# Arm_Schematic.net
KiCad netlist of a schematic drawn in Altium Designer
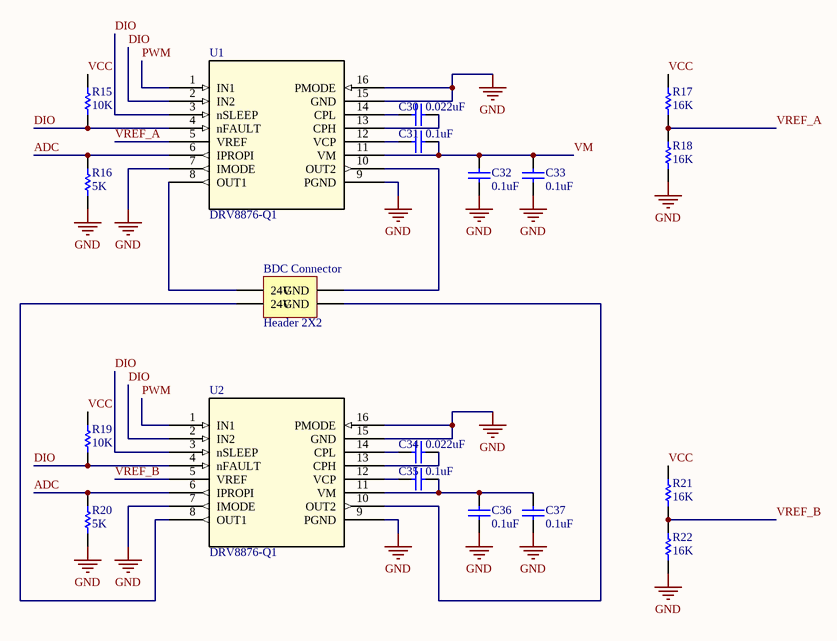
[diagram p0: Arm Schematic.SchDoc]

(export (version "E")
  (design (tool "Eeschema 10.0.6"))
  (components
    (comp (ref "BDC Connector")
      (value "Header 2X2")
      (footprint "MHDR2X2")
      (description "Header, 2-Pin, Dual row")
      (fields (field (name "PUBLISHER") "Altium Limited"))
      (libsource (lib "Miscellaneous Connectors") (part "MHDR2X2"))
    )
    (comp (ref "C30")
      (value "0.022uF")
      (footprint "CAP_1206")
      (description "Capacitor 1208 22uF")
      (fields
        (field (name "MANUFACTURER") "Samsung Electro-Mechanics America, Inc")
        (field (name "MANUFACTURER PART NUMBER") "CL31A226MOCLNNC")
      )
      (libsource (lib "Capacitors") (part "22uF_16V_1208"))
    )
    (comp (ref "C31")
      (value "0.1uF")
      (footprint "CAP_1206")
      (description "Capacitor 1208 22uF")
      (fields
        (field (name "MANUFACTURER") "Samsung Electro-Mechanics America, Inc")
        (field (name "MANUFACTURER PART NUMBER") "CL31A226MOCLNNC")
      )
      (libsource (lib "Capacitors") (part "22uF_16V_1208"))
    )
    (comp (ref "C32")
      (value "0.1uF")
      (footprint "CAP_1206")
      (description "Capacitor 1208 22uF")
      (fields
        (field (name "MANUFACTURER") "Samsung Electro-Mechanics America, Inc")
        (field (name "MANUFACTURER PART NUMBER") "CL31A226MOCLNNC")
      )
      (libsource (lib "Capacitors") (part "22uF_16V_1208"))
    )
    (comp (ref "C33")
      (value "0.1uF")
      (footprint "CAP_1206")
      (description "Capacitor 1208 22uF")
      (fields
        (field (name "MANUFACTURER") "Samsung Electro-Mechanics America, Inc")
        (field (name "MANUFACTURER PART NUMBER") "CL31A226MOCLNNC")
      )
      (libsource (lib "Capacitors") (part "22uF_16V_1208"))
    )
    (comp (ref "C34")
      (value "0.022uF")
      (footprint "CAP_1206")
      (description "Capacitor 1208 22uF")
      (fields
        (field (name "MANUFACTURER") "Samsung Electro-Mechanics America, Inc")
        (field (name "MANUFACTURER PART NUMBER") "CL31A226MOCLNNC")
      )
      (libsource (lib "Capacitors") (part "22uF_16V_1208"))
    )
    (comp (ref "C35")
      (value "0.1uF")
      (footprint "CAP_1206")
      (description "Capacitor 1208 22uF")
      (fields
        (field (name "MANUFACTURER") "Samsung Electro-Mechanics America, Inc")
        (field (name "MANUFACTURER PART NUMBER") "CL31A226MOCLNNC")
      )
      (libsource (lib "Capacitors") (part "22uF_16V_1208"))
    )
    (comp (ref "C36")
      (value "0.1uF")
      (footprint "CAP_1206")
      (description "Capacitor 1208 22uF")
      (fields
        (field (name "MANUFACTURER") "Samsung Electro-Mechanics America, Inc")
        (field (name "MANUFACTURER PART NUMBER") "CL31A226MOCLNNC")
      )
      (libsource (lib "Capacitors") (part "22uF_16V_1208"))
    )
    (comp (ref "C37")
      (value "0.1uF")
      (footprint "CAP_1206")
      (description "Capacitor 1208 22uF")
      (fields
        (field (name "MANUFACTURER") "Samsung Electro-Mechanics America, Inc")
        (field (name "MANUFACTURER PART NUMBER") "CL31A226MOCLNNC")
      )
      (libsource (lib "Capacitors") (part "22uF_16V_1208"))
    )
    (comp (ref "R15")
      (value "10K")
      (footprint "AXIAL-0.3")
      (description "Resistor")
      (fields (field (name "PUBLISHER") "Altium Limited"))
      (libsource (lib "Miscellaneous Devices") (part "Res1"))
    )
    (comp (ref "R16")
      (value "5K")
      (footprint "AXIAL-0.3")
      (description "Resistor")
      (fields (field (name "PUBLISHER") "Altium Limited"))
      (libsource (lib "Miscellaneous Devices") (part "Res1"))
    )
    (comp (ref "R17")
      (value "16K")
      (footprint "AXIAL-0.3")
      (description "Resistor")
      (fields (field (name "PUBLISHER") "Altium Limited"))
      (libsource (lib "Miscellaneous Devices") (part "Res1"))
    )
    (comp (ref "R18")
      (value "16K")
      (footprint "AXIAL-0.3")
      (description "Resistor")
      (fields (field (name "PUBLISHER") "Altium Limited"))
      (libsource (lib "Miscellaneous Devices") (part "Res1"))
    )
    (comp (ref "R19")
      (value "10K")
      (footprint "AXIAL-0.3")
      (description "Resistor")
      (fields (field (name "PUBLISHER") "Altium Limited"))
      (libsource (lib "Miscellaneous Devices") (part "Res1"))
    )
    (comp (ref "R20")
      (value "5K")
      (footprint "AXIAL-0.3")
      (description "Resistor")
      (fields (field (name "PUBLISHER") "Altium Limited"))
      (libsource (lib "Miscellaneous Devices") (part "Res1"))
    )
    (comp (ref "R21")
      (value "16K")
      (footprint "AXIAL-0.3")
      (description "Resistor")
      (fields (field (name "PUBLISHER") "Altium Limited"))
      (libsource (lib "Miscellaneous Devices") (part "Res1"))
    )
    (comp (ref "R22")
      (value "16K")
      (footprint "AXIAL-0.3")
      (description "Resistor")
      (fields (field (name "PUBLISHER") "Altium Limited"))
      (libsource (lib "Miscellaneous Devices") (part "Res1"))
    )
    (comp (ref "U1")
      (value "DRV8876-Q1")
      (footprint "SOIC_PWPRQ1_TEX")
      (description "No Description Available")
      (fields
        (field (name "MANUFACTURER_PART_NUMBER") "DRV8876QPWPRQ1")
        (field (name "COPYRIGHT") "Copyright (C) 2018 Accelerated Designs. All rights reserved")
      )
      (libsource (lib "2020-08-08_18-29-37") (part "DRV8876QPWPRQ1"))
    )
    (comp (ref "U2")
      (value "DRV8876-Q1")
      (footprint "SOIC_PWPRQ1_TEX")
      (description "No Description Available")
      (fields
        (field (name "MANUFACTURER_PART_NUMBER") "DRV8876QPWPRQ1")
        (field (name "COPYRIGHT") "Copyright (C) 2018 Accelerated Designs. All rights reserved")
      )
      (libsource (lib "2020-08-08_18-29-37") (part "DRV8876QPWPRQ1"))
    )
  )
  (nets
    (net (code "1") (name "/ADC") (class "Default")
      (node (ref "R16") (pin "2") (pinfunction "2_2") (pintype "passive"))
      (node (ref "R20") (pin "2") (pinfunction "2_2") (pintype "passive"))
      (node (ref "U1") (pin "6") (pinfunction "IPROPI_6") (pintype "output"))
      (node (ref "U2") (pin "6") (pinfunction "IPROPI_6") (pintype "output"))
    )
    (net (code "2") (name "/DIO") (class "Default")
      (node (ref "R15") (pin "1") (pinfunction "1_1") (pintype "passive"))
      (node (ref "R19") (pin "1") (pinfunction "1_1") (pintype "passive"))
      (node (ref "U1") (pin "2") (pinfunction "IN2_2") (pintype "input"))
      (node (ref "U1") (pin "3") (pinfunction "nSLEEP_3") (pintype "input"))
      (node (ref "U1") (pin "4") (pinfunction "nFAULT_4") (pintype "input"))
      (node (ref "U2") (pin "2") (pinfunction "IN2_2") (pintype "input"))
      (node (ref "U2") (pin "3") (pinfunction "nSLEEP_3") (pintype "input"))
      (node (ref "U2") (pin "4") (pinfunction "nFAULT_4") (pintype "input"))
    )
    (net (code "3") (name "/PWM") (class "Default")
      (node (ref "U1") (pin "1") (pinfunction "IN1_1") (pintype "input"))
      (node (ref "U2") (pin "1") (pinfunction "IN1_1") (pintype "input"))
    )
    (net (code "4") (name "/VCC") (class "Default")
      (node (ref "R15") (pin "2") (pinfunction "2_2") (pintype "passive"))
      (node (ref "R17") (pin "2") (pinfunction "2_2") (pintype "passive"))
      (node (ref "R19") (pin "2") (pinfunction "2_2") (pintype "passive"))
      (node (ref "R21") (pin "2") (pinfunction "2_2") (pintype "passive"))
    )
    (net (code "5") (name "/VM") (class "Default")
      (node (ref "C31") (pin "2") (pinfunction "2_2") (pintype "passive"))
      (node (ref "C32") (pin "2") (pinfunction "2_2") (pintype "passive"))
      (node (ref "C33") (pin "2") (pinfunction "2_2") (pintype "passive"))
      (node (ref "U1") (pin "11") (pinfunction "VM_11") (pintype "power_in"))
    )
    (net (code "6") (name "/VREF_A") (class "Default")
      (node (ref "R17") (pin "1") (pinfunction "1_1") (pintype "passive"))
      (node (ref "R18") (pin "2") (pinfunction "2_2") (pintype "passive"))
      (node (ref "U1") (pin "5") (pinfunction "VREF_5") (pintype "power_in"))
    )
    (net (code "7") (name "/VREF_B") (class "Default")
      (node (ref "R21") (pin "1") (pinfunction "1_1") (pintype "passive"))
      (node (ref "R22") (pin "2") (pinfunction "2_2") (pintype "passive"))
      (node (ref "U2") (pin "5") (pinfunction "VREF_5") (pintype "power_in"))
    )
    (net (code "8") (name "GND") (class "Default")
      (node (ref "C32") (pin "1") (pinfunction "1_1") (pintype "passive"))
      (node (ref "C33") (pin "1") (pinfunction "1_1") (pintype "passive"))
      (node (ref "C36") (pin "1") (pinfunction "1_1") (pintype "passive"))
      (node (ref "C37") (pin "1") (pinfunction "1_1") (pintype "passive"))
      (node (ref "R16") (pin "1") (pinfunction "1_1") (pintype "passive"))
      (node (ref "R18") (pin "1") (pinfunction "1_1") (pintype "passive"))
      (node (ref "R20") (pin "1") (pinfunction "1_1") (pintype "passive"))
      (node (ref "R22") (pin "1") (pinfunction "1_1") (pintype "passive"))
      (node (ref "U1") (pin "15") (pinfunction "GND_15") (pintype "passive"))
      (node (ref "U1") (pin "16") (pinfunction "PMODE_16") (pintype "input"))
      (node (ref "U1") (pin "7") (pinfunction "IMODE_7") (pintype "output"))
      (node (ref "U1") (pin "9") (pinfunction "PGND_9") (pintype "passive"))
      (node (ref "U2") (pin "15") (pinfunction "GND_15") (pintype "passive"))
      (node (ref "U2") (pin "16") (pinfunction "PMODE_16") (pintype "input"))
      (node (ref "U2") (pin "7") (pinfunction "IMODE_7") (pintype "output"))
      (node (ref "U2") (pin "9") (pinfunction "PGND_9") (pintype "passive"))
    )
    (net (code "9") (name "Net-(U1-CPH)") (class "Default")
      (node (ref "C30") (pin "2") (pinfunction "2_2") (pintype "passive"))
      (node (ref "U1") (pin "13") (pinfunction "CPH_13") (pintype "passive"))
    )
    (net (code "10") (name "Net-(U1-CPL)") (class "Default")
      (node (ref "C30") (pin "1") (pinfunction "1_1") (pintype "passive"))
      (node (ref "U1") (pin "14") (pinfunction "CPL_14") (pintype "passive"))
    )
    (net (code "11") (name "Net-(U1-OUT1)") (class "Default")
      (node (ref "BDC Connector") (pin "1") (pinfunction "24V_1") (pintype "passive"))
      (node (ref "U1") (pin "8") (pinfunction "OUT1_8") (pintype "output"))
    )
    (net (code "12") (name "Net-(U1-OUT2)") (class "Default")
      (node (ref "BDC Connector") (pin "2") (pinfunction "GND_2") (pintype "passive"))
      (node (ref "U1") (pin "10") (pinfunction "OUT2_10") (pintype "output"))
    )
    (net (code "13") (name "Net-(U1-VCP)") (class "Default")
      (node (ref "C31") (pin "1") (pinfunction "1_1") (pintype "passive"))
      (node (ref "U1") (pin "12") (pinfunction "VCP_12") (pintype "power_in"))
    )
    (net (code "14") (name "Net-(U2-CPH)") (class "Default")
      (node (ref "C34") (pin "2") (pinfunction "2_2") (pintype "passive"))
      (node (ref "U2") (pin "13") (pinfunction "CPH_13") (pintype "passive"))
    )
    (net (code "15") (name "Net-(U2-CPL)") (class "Default")
      (node (ref "C34") (pin "1") (pinfunction "1_1") (pintype "passive"))
      (node (ref "U2") (pin "14") (pinfunction "CPL_14") (pintype "passive"))
    )
    (net (code "16") (name "Net-(U2-OUT1)") (class "Default")
      (node (ref "BDC Connector") (pin "3") (pinfunction "24V_3") (pintype "passive"))
      (node (ref "U2") (pin "8") (pinfunction "OUT1_8") (pintype "output"))
    )
    (net (code "17") (name "Net-(U2-OUT2)") (class "Default")
      (node (ref "BDC Connector") (pin "4") (pinfunction "GND_4") (pintype "passive"))
      (node (ref "U2") (pin "10") (pinfunction "OUT2_10") (pintype "output"))
    )
    (net (code "18") (name "Net-(U2-VCP)") (class "Default")
      (node (ref "C35") (pin "1") (pinfunction "1_1") (pintype "passive"))
      (node (ref "U2") (pin "12") (pinfunction "VCP_12") (pintype "power_in"))
    )
    (net (code "19") (name "Net-(U2-VM)") (class "Default")
      (node (ref "C35") (pin "2") (pinfunction "2_2") (pintype "passive"))
      (node (ref "C36") (pin "2") (pinfunction "2_2") (pintype "passive"))
      (node (ref "C37") (pin "2") (pinfunction "2_2") (pintype "passive"))
      (node (ref "U2") (pin "11") (pinfunction "VM_11") (pintype "power_in"))
    )
  )
)
